# 03__Board_Power.net
KiCad netlist of a schematic drawn in Altium Designer
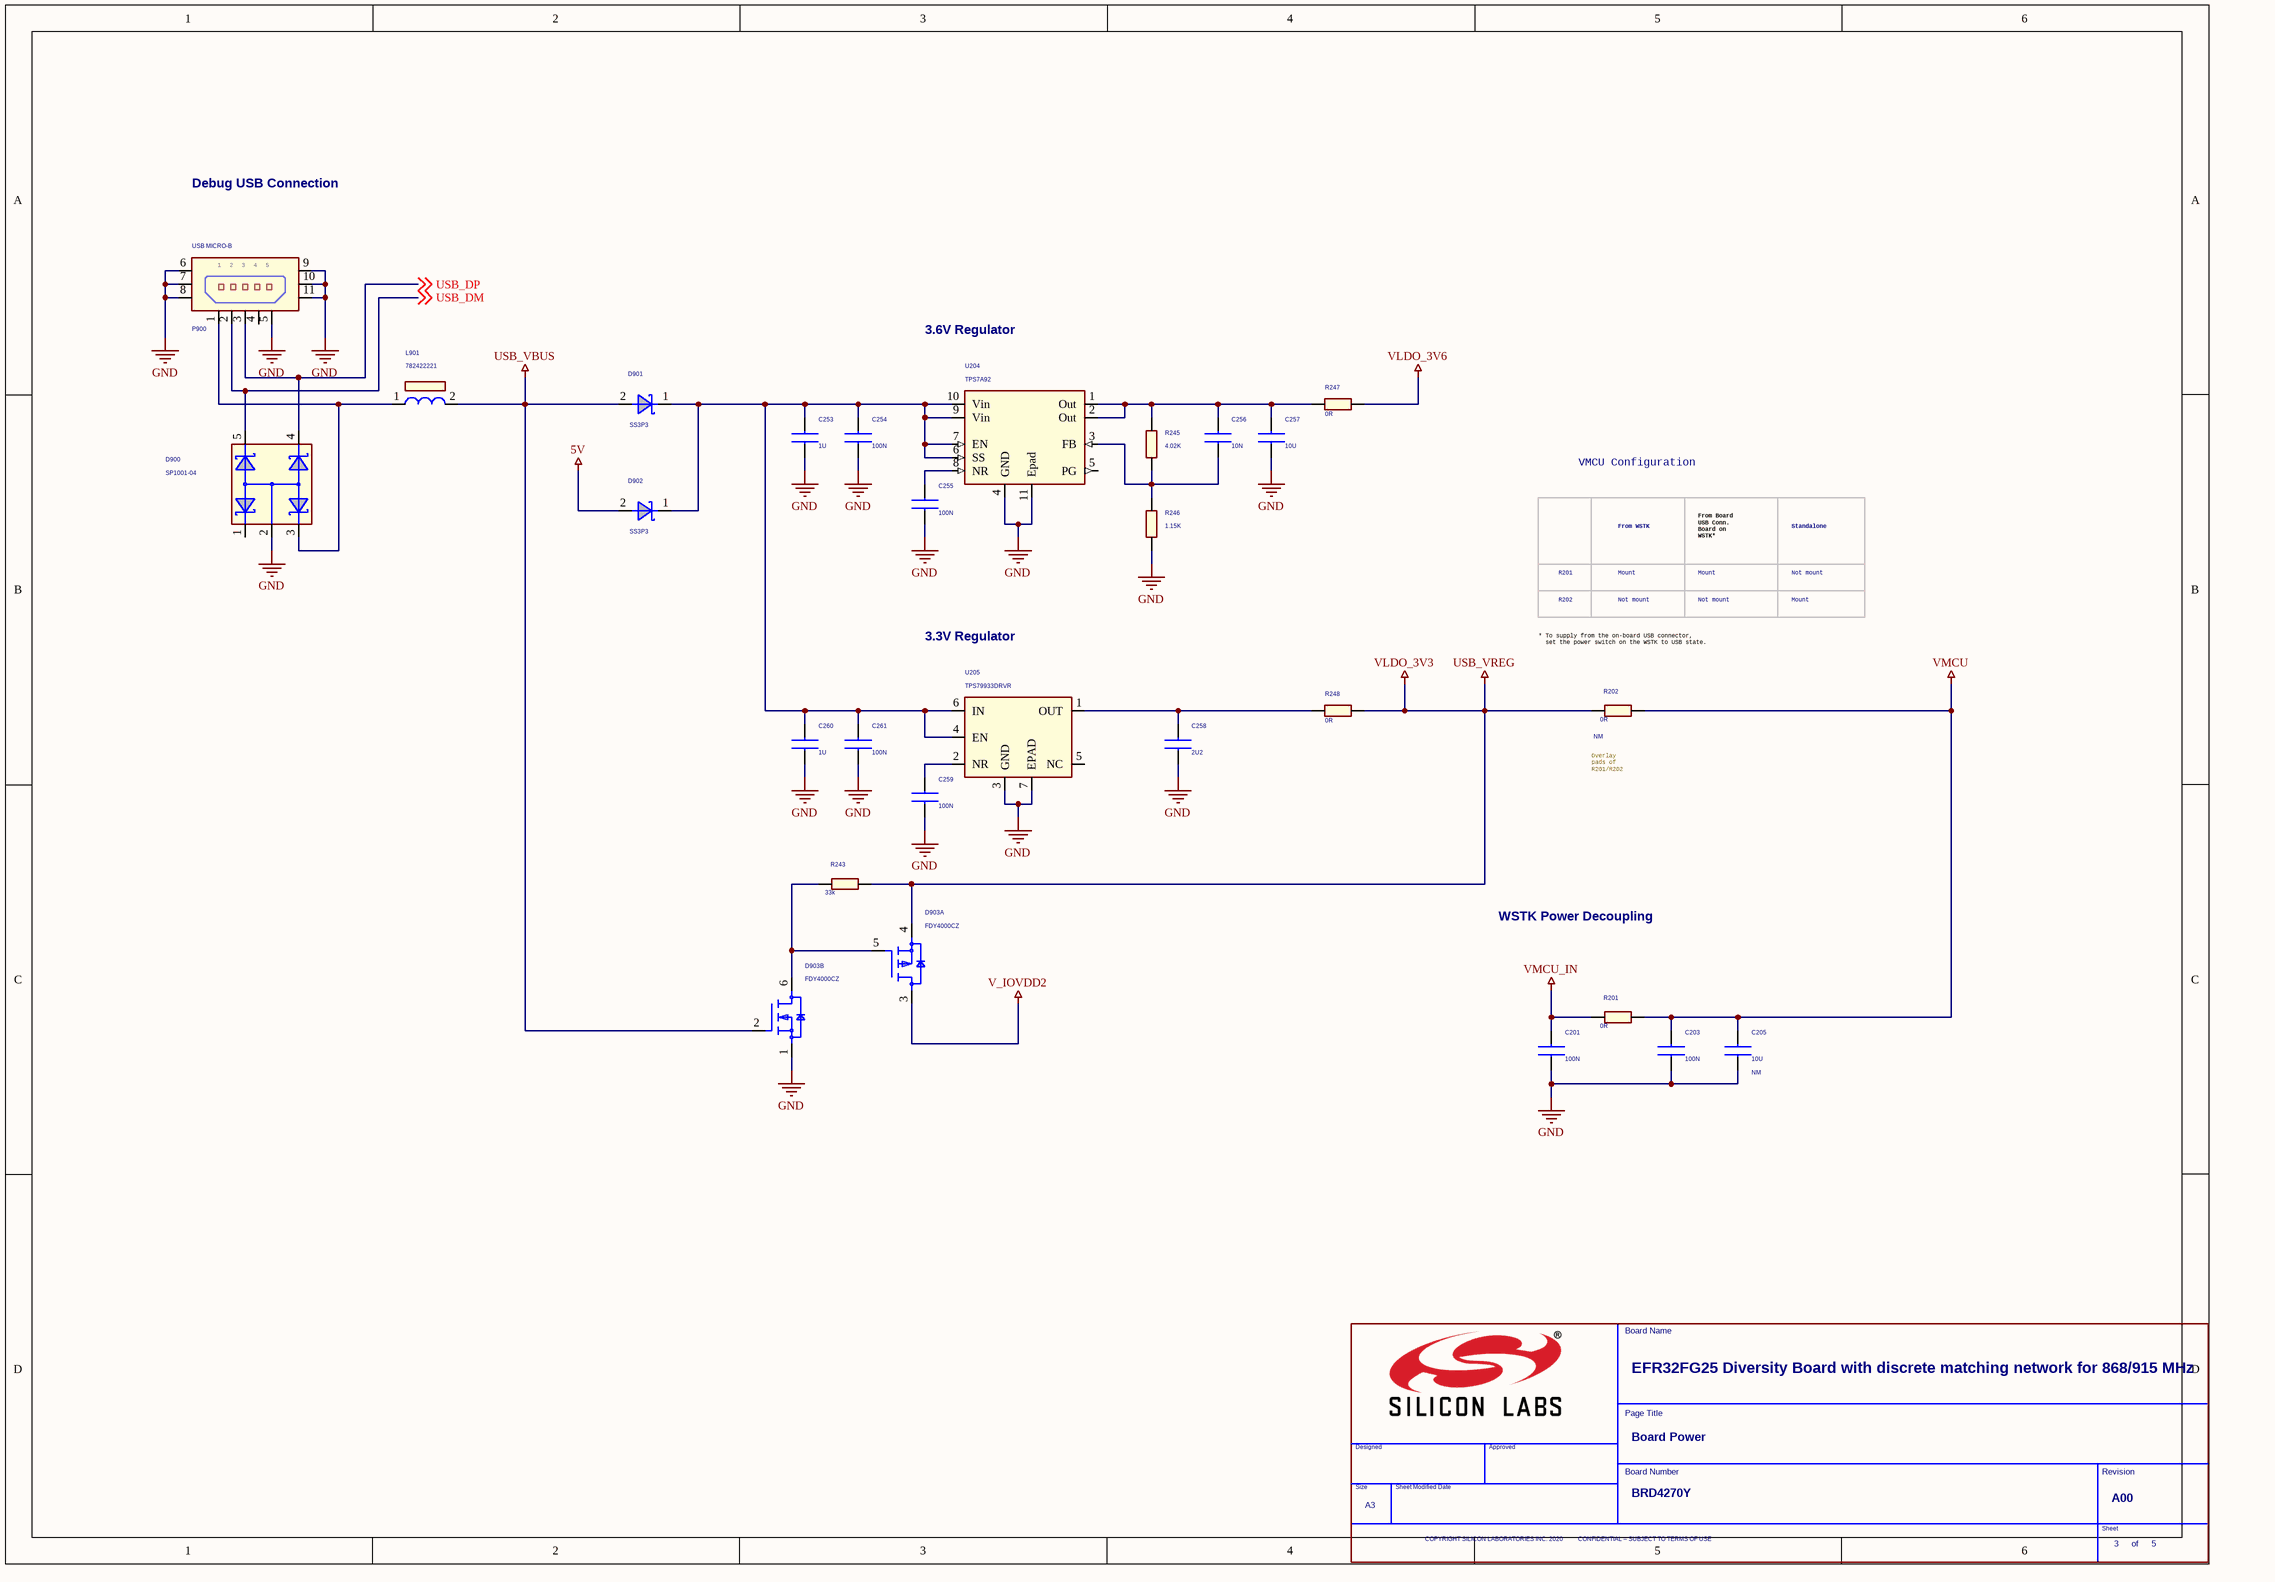
[diagram p0: 03_ Board Power.SchDoc]

(export (version "E")
  (design (tool "Eeschema 10.0.6"))
  (components
    (comp (ref "C201")
      (value "100N")
      (footprint "C0201_L")
      (fields (field (name "TOLERANCE") "20%"))
      (libsource (lib "*") (part "C0201"))
    )
    (comp (ref "C203")
      (value "100N")
      (footprint "C0201_L")
      (fields (field (name "TOLERANCE") "20%"))
      (libsource (lib "*") (part "C0201"))
    )
    (comp (ref "C205")
      (value "10U")
      (footprint "T_UNDEF")
      (fields (field (name "NOT MOUNTED") "NM"))
      (libsource (lib "*") (part "CAPACITOR"))
    )
    (comp (ref "C253")
      (value "1U")
      (footprint "C0402_L")
      (fields (field (name "TOLERANCE") "10%"))
      (libsource (lib "*") (part "C0402"))
    )
    (comp (ref "C254")
      (value "100N")
      (footprint "C0201_L")
      (fields (field (name "TOLERANCE") "20%"))
      (libsource (lib "*") (part "C0201"))
    )
    (comp (ref "C255")
      (value "100N")
      (footprint "C0201_L")
      (fields (field (name "TOLERANCE") "20%"))
      (libsource (lib "*") (part "C0201"))
    )
    (comp (ref "C256")
      (value "10N")
      (footprint "C0201_L")
      (fields (field (name "TOLERANCE") "10%"))
      (libsource (lib "*") (part "C0201"))
    )
    (comp (ref "C257")
      (value "10U")
      (footprint "C0402_L")
      (fields (field (name "TOLERANCE") "20%"))
      (libsource (lib "*") (part "C0402"))
    )
    (comp (ref "C258")
      (value "2U2")
      (footprint "C0402_L")
      (fields (field (name "TOLERANCE") "10%"))
      (libsource (lib "*") (part "C0402"))
    )
    (comp (ref "C259")
      (value "100N")
      (footprint "C0201_L")
      (fields (field (name "TOLERANCE") "20%"))
      (libsource (lib "*") (part "C0201"))
    )
    (comp (ref "C260")
      (value "1U")
      (footprint "C0402_L")
      (fields (field (name "TOLERANCE") "10%"))
      (libsource (lib "*") (part "C0402"))
    )
    (comp (ref "C261")
      (value "100N")
      (footprint "C0201_L")
      (fields (field (name "TOLERANCE") "20%"))
      (libsource (lib "*") (part "C0201"))
    )
    (comp (ref "D900")
      (value "SP1001-04")
      (footprint "SOT553_L")
      (fields (field (name "MFG") "Littlefuse"))
      (libsource (lib "*") (part "SP1001-04"))
    )
    (comp (ref "D901")
      (value "SS3P3")
      (footprint "DO-220AA")
      (fields (field (name "MFG") "Vishay"))
      (libsource (lib "*") (part "SS3P3"))
    )
    (comp (ref "D902")
      (value "SS3P3")
      (footprint "DO-220AA")
      (fields (field (name "MFG") "Vishay"))
      (libsource (lib "*") (part "SS3P3"))
    )
    (comp (ref "D903")
      (value "FDY4000CZ")
      (footprint "SOT-563")
      (fields (field (name "MFG") "ON Semiconductor"))
      (libsource (lib "*") (part "FDY4000CZ"))
    )
    (comp (ref "L901")
      (value "782422221")
      (footprint "COIL_0402")
      (fields (field (name "MFG") "Würth Elektronik"))
      (libsource (lib "*") (part "WE-CBA"))
    )
    (comp (ref "P900")
      (value "USB MICRO-B")
      (footprint "AMP_FCI_10118194")
      (fields (field (name "MFG") "KLS"))
      (libsource (lib "BRD4270Y_Library") (part "KLS L-KLS1-238-0-0-0"))
    )
    (comp (ref "R201") (value "0R") (footprint "R0402_L") (libsource (lib "*") (part "R0402")))
    (comp (ref "R202")
      (value "0R")
      (footprint "R0402_L")
      (fields (field (name "NOT MOUNTED") "NM"))
      (libsource (lib "*") (part "R0402"))
    )
    (comp (ref "R243") (value "33k") (footprint "R0402_L") (libsource (lib "*") (part "R0402")))
    (comp (ref "R245") (value "4.02K") (footprint "R0201_L") (libsource (lib "*") (part "R0201")))
    (comp (ref "R246") (value "1.15K") (footprint "R0201_L") (libsource (lib "*") (part "R0201")))
    (comp (ref "R247") (value "0R") (footprint "R0603_L") (libsource (lib "*") (part "R0603")))
    (comp (ref "R248") (value "0R") (footprint "R0603_L") (libsource (lib "*") (part "R0603")))
    (comp (ref "U204")
      (value "TPS7A92")
      (footprint "WFDFN-10_EP_TPS7A92")
      (fields (field (name "MFG") "Texas Instruments"))
      (libsource (lib "*") (part "TPS7A92"))
    )
    (comp (ref "U205")
      (value "TPS79933DRVR")
      (footprint "SON-6_EP_TPS79933DDCR")
      (fields (field (name "MFG") "Texas Instruments"))
      (libsource (lib "*") (part "TPS79933DRVR"))
    )
  )
  (nets
    (net (code "1") (name "5V") (class "Default")
      (node (ref "D902") (pin "2") (pinfunction "Anode_2") (pintype "passive"))
    )
    (net (code "2") (name "GND") (class "Default")
      (node (ref "C201") (pin "2") (pinfunction "2_2") (pintype "passive"))
      (node (ref "C203") (pin "2") (pinfunction "2_2") (pintype "passive"))
      (node (ref "C205") (pin "2") (pinfunction "2_2") (pintype "passive"))
      (node (ref "C253") (pin "2") (pinfunction "2_2") (pintype "passive"))
      (node (ref "C254") (pin "2") (pinfunction "2_2") (pintype "passive"))
      (node (ref "C255") (pin "2") (pinfunction "2_2") (pintype "passive"))
      (node (ref "C257") (pin "2") (pinfunction "2_2") (pintype "passive"))
      (node (ref "C258") (pin "2") (pinfunction "2_2") (pintype "passive"))
      (node (ref "C259") (pin "2") (pinfunction "2_2") (pintype "passive"))
      (node (ref "C260") (pin "2") (pinfunction "2_2") (pintype "passive"))
      (node (ref "C261") (pin "2") (pinfunction "2_2") (pintype "passive"))
      (node (ref "D900") (pin "2") (pinfunction "2_2") (pintype "passive"))
      (node (ref "D903") (pin "1") (pinfunction "S1_1") (pintype "passive"))
      (node (ref "P900") (pin "10") (pinfunction "10_10") (pintype "passive"))
      (node (ref "P900") (pin "11") (pinfunction "11_11") (pintype "passive"))
      (node (ref "P900") (pin "5") (pinfunction "5_5") (pintype "passive"))
      (node (ref "P900") (pin "6") (pinfunction "6_6") (pintype "passive"))
      (node (ref "P900") (pin "7") (pinfunction "7_7") (pintype "passive"))
      (node (ref "P900") (pin "8") (pinfunction "8_8") (pintype "passive"))
      (node (ref "P900") (pin "9") (pinfunction "9_9") (pintype "passive"))
      (node (ref "R246") (pin "1") (pinfunction "1_1") (pintype "passive"))
      (node (ref "U204") (pin "11") (pinfunction "Epad_11") (pintype "power_in"))
      (node (ref "U204") (pin "4") (pinfunction "GND_4") (pintype "power_in"))
      (node (ref "U205") (pin "3") (pinfunction "GND_3") (pintype "passive"))
      (node (ref "U205") (pin "7") (pinfunction "EPAD_7") (pintype "passive"))
    )
    (net (code "3") (name "Net-(C256-Pad1)") (class "Default")
      (node (ref "C256") (pin "1") (pinfunction "1_1") (pintype "passive"))
      (node (ref "C257") (pin "1") (pinfunction "1_1") (pintype "passive"))
      (node (ref "R245") (pin "2") (pinfunction "2_2") (pintype "passive"))
      (node (ref "R247") (pin "1") (pinfunction "1_1") (pintype "passive"))
      (node (ref "U204") (pin "1") (pinfunction "Out_1") (pintype "power_in"))
      (node (ref "U204") (pin "2") (pinfunction "Out_2") (pintype "power_in"))
    )
    (net (code "4") (name "Net-(D900-Pad3)") (class "Default")
      (node (ref "D900") (pin "3") (pinfunction "3_3") (pintype "passive"))
      (node (ref "L901") (pin "1") (pinfunction "1_1") (pintype "passive"))
      (node (ref "P900") (pin "1") (pinfunction "1_1") (pintype "passive"))
    )
    (net (code "5") (name "Net-(D901-Cathode)") (class "Default")
      (node (ref "C253") (pin "1") (pinfunction "1_1") (pintype "passive"))
      (node (ref "C254") (pin "1") (pinfunction "1_1") (pintype "passive"))
      (node (ref "C260") (pin "1") (pinfunction "1_1") (pintype "passive"))
      (node (ref "C261") (pin "1") (pinfunction "1_1") (pintype "passive"))
      (node (ref "D901") (pin "1") (pinfunction "Cathode_1") (pintype "passive"))
      (node (ref "D902") (pin "1") (pinfunction "Cathode_1") (pintype "passive"))
      (node (ref "U204") (pin "10") (pinfunction "Vin_10") (pintype "power_in"))
      (node (ref "U204") (pin "6") (pinfunction "SS_6") (pintype "input"))
      (node (ref "U204") (pin "7") (pinfunction "EN_7") (pintype "input"))
      (node (ref "U204") (pin "9") (pinfunction "Vin_9") (pintype "power_in"))
      (node (ref "U205") (pin "4") (pinfunction "EN_4") (pintype "passive"))
      (node (ref "U205") (pin "6") (pinfunction "IN_6") (pintype "passive"))
    )
    (net (code "6") (name "Net-(D903A-G5)") (class "Default")
      (node (ref "D903") (pin "5") (pinfunction "G5_5") (pintype "passive"))
      (node (ref "D903") (pin "6") (pinfunction "D1_6") (pintype "passive"))
      (node (ref "R243") (pin "2") (pinfunction "2_2") (pintype "passive"))
    )
    (net (code "7") (name "Net-(U204-FB)") (class "Default")
      (node (ref "C256") (pin "2") (pinfunction "2_2") (pintype "passive"))
      (node (ref "R245") (pin "1") (pinfunction "1_1") (pintype "passive"))
      (node (ref "R246") (pin "2") (pinfunction "2_2") (pintype "passive"))
      (node (ref "U204") (pin "3") (pinfunction "FB_3") (pintype "input"))
    )
    (net (code "8") (name "Net-(U204-NR)") (class "Default")
      (node (ref "C255") (pin "1") (pinfunction "1_1") (pintype "passive"))
      (node (ref "U204") (pin "8") (pinfunction "NR_8") (pintype "input"))
    )
    (net (code "9") (name "Net-(U205-NR)") (class "Default")
      (node (ref "C259") (pin "1") (pinfunction "1_1") (pintype "passive"))
      (node (ref "U205") (pin "2") (pinfunction "NR_2") (pintype "passive"))
    )
    (net (code "10") (name "Net-(U205-OUT)") (class "Default")
      (node (ref "C258") (pin "1") (pinfunction "1_1") (pintype "passive"))
      (node (ref "R248") (pin "1") (pinfunction "1_1") (pintype "passive"))
      (node (ref "U205") (pin "1") (pinfunction "OUT_1") (pintype "passive"))
    )
    (net (code "11") (name "USB_DM") (class "Default")
      (node (ref "D900") (pin "5") (pinfunction "5_5") (pintype "passive"))
      (node (ref "P900") (pin "2") (pinfunction "2_2") (pintype "passive"))
    )
    (net (code "12") (name "USB_DP") (class "Default")
      (node (ref "D900") (pin "4") (pinfunction "4_4") (pintype "passive"))
      (node (ref "P900") (pin "3") (pinfunction "3_3") (pintype "passive"))
    )
    (net (code "13") (name "USB_VBUS") (class "Default")
      (node (ref "D901") (pin "2") (pinfunction "Anode_2") (pintype "passive"))
      (node (ref "D903") (pin "2") (pinfunction "G1_2") (pintype "passive"))
      (node (ref "L901") (pin "2") (pinfunction "2_2") (pintype "passive"))
    )
    (net (code "14") (name "USB_VREG") (class "Default")
      (node (ref "D903") (pin "4") (pinfunction "S2_4") (pintype "passive"))
      (node (ref "R202") (pin "2") (pinfunction "2_2") (pintype "passive"))
      (node (ref "R243") (pin "1") (pinfunction "1_1") (pintype "passive"))
      (node (ref "R248") (pin "2") (pinfunction "2_2") (pintype "passive"))
    )
    (net (code "15") (name "VLDO_3V6") (class "Default")
      (node (ref "R247") (pin "2") (pinfunction "2_2") (pintype "passive"))
    )
    (net (code "16") (name "VMCU") (class "Default")
      (node (ref "C203") (pin "1") (pinfunction "1_1") (pintype "passive"))
      (node (ref "C205") (pin "1") (pinfunction "1_1") (pintype "passive"))
      (node (ref "R201") (pin "1") (pinfunction "1_1") (pintype "passive"))
      (node (ref "R202") (pin "1") (pinfunction "1_1") (pintype "passive"))
    )
    (net (code "17") (name "VMCU_IN") (class "Default")
      (node (ref "C201") (pin "1") (pinfunction "1_1") (pintype "passive"))
      (node (ref "R201") (pin "2") (pinfunction "2_2") (pintype "passive"))
    )
    (net (code "18") (name "V_IOVDD2") (class "Default")
      (node (ref "D903") (pin "3") (pinfunction "D2_3") (pintype "passive"))
    )
    (net (code "19") (name "unconnected-(D900-Pad1)") (class "Default")
      (node (ref "D900") (pin "1") (pinfunction "1_1") (pintype "passive"))
    )
    (net (code "20") (name "unconnected-(P900-Pad4)") (class "Default")
      (node (ref "P900") (pin "4") (pinfunction "4_4") (pintype "passive"))
    )
    (net (code "21") (name "unconnected-(U204-PG-Pad5)") (class "Default")
      (node (ref "U204") (pin "5") (pinfunction "PG_5") (pintype "output"))
    )
    (net (code "22") (name "unconnected-(U205-NC-Pad5)") (class "Default")
      (node (ref "U205") (pin "5") (pinfunction "NC_5") (pintype "passive"))
    )
  )
)
